# eurorack-passive-multiple.net
KiCad netlist of a schematic drawn in EAGLE
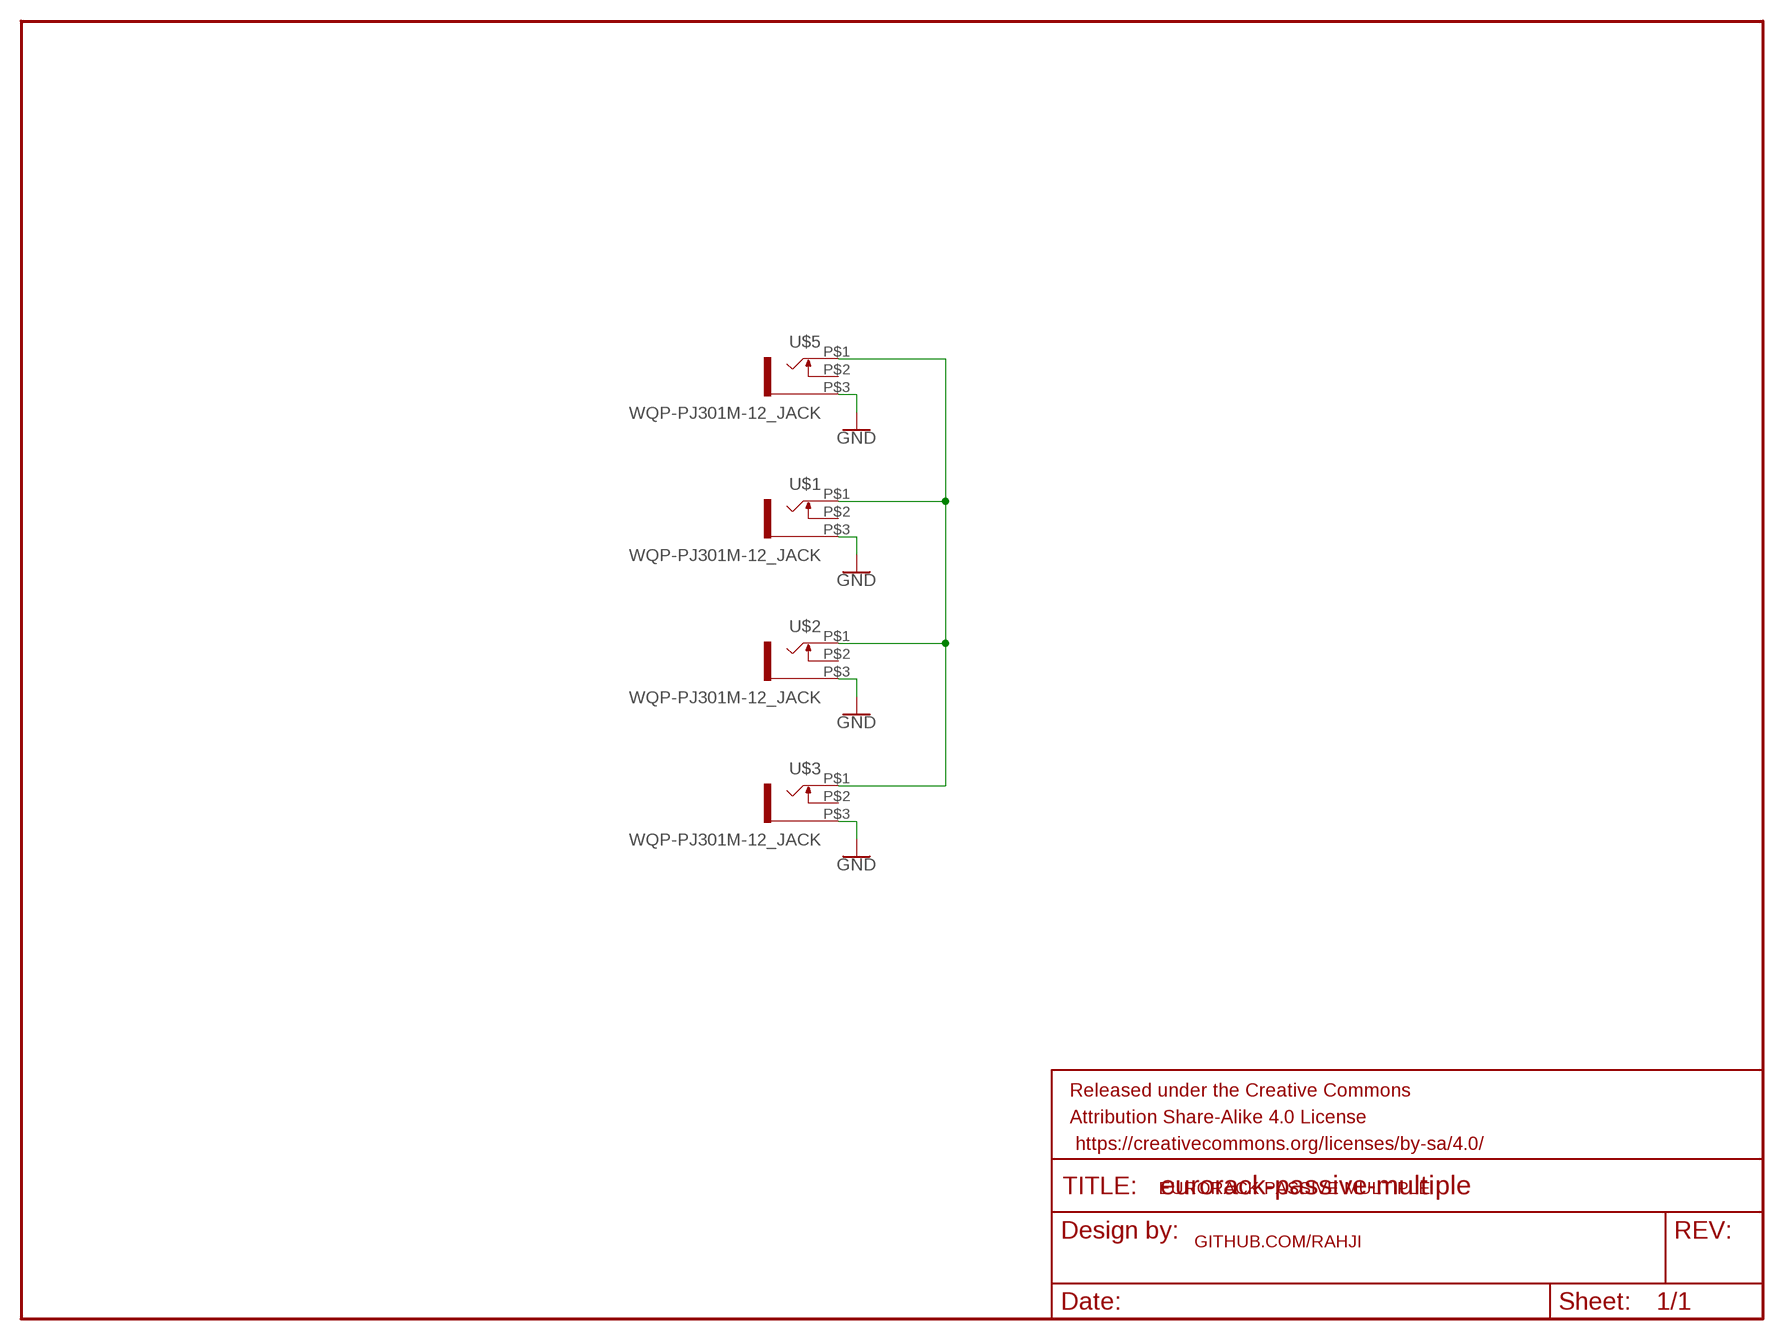
[diagram p0: schematic, sheet 1]

(export (version "E")
  (design (tool "Eeschema 10.0.6"))
  (components
    (comp (ref "FRAME1")
      (value "FRAME-LETTERNO_PACKAGE")
      (footprint "eagle-import:DUMMY")
      (fields (field (name "DESIGNER") "Nobody"))
      (libsource (lib "eagle-import") (part "FRAME-LETTERNO_PACKAGE"))
    )
    (comp (ref "U$1")
      (value "WQP-PJ301M-12_JACK")
      (footprint "eagle-import:WQP-PJ301M-12_JACK")
      (libsource (lib "eagle-import") (part "WQP-PJ301M-12_JACK"))
    )
    (comp (ref "U$2")
      (value "WQP-PJ301M-12_JACK")
      (footprint "eagle-import:WQP-PJ301M-12_JACK")
      (libsource (lib "eagle-import") (part "WQP-PJ301M-12_JACK"))
    )
    (comp (ref "U$3")
      (value "WQP-PJ301M-12_JACK")
      (footprint "eagle-import:WQP-PJ301M-12_JACK")
      (libsource (lib "eagle-import") (part "WQP-PJ301M-12_JACK"))
    )
    (comp (ref "U$5")
      (value "WQP-PJ301M-12_JACK")
      (footprint "eagle-import:WQP-PJ301M-12_JACK")
      (libsource (lib "eagle-import") (part "WQP-PJ301M-12_JACK"))
    )
  )
  (nets
    (net (code "1") (name "GND") (class "Default")
      (node (ref "U$1") (pin "P$3") (pinfunction "1_P$3") (pintype "passive"))
      (node (ref "U$2") (pin "P$3") (pinfunction "1_P$3") (pintype "passive"))
      (node (ref "U$3") (pin "P$3") (pinfunction "1_P$3") (pintype "passive"))
      (node (ref "U$5") (pin "P$3") (pinfunction "1_P$3") (pintype "passive"))
    )
    (net (code "2") (name "Net-(U$1-2)") (class "Default")
      (node (ref "U$1") (pin "P$1") (pinfunction "2_P$1") (pintype "passive"))
      (node (ref "U$2") (pin "P$1") (pinfunction "2_P$1") (pintype "passive"))
      (node (ref "U$3") (pin "P$1") (pinfunction "2_P$1") (pintype "passive"))
      (node (ref "U$5") (pin "P$1") (pinfunction "2_P$1") (pintype "passive"))
    )
    (net (code "3") (name "unconnected-(U$1-3-PadP$2)") (class "Default")
      (node (ref "U$1") (pin "P$2") (pinfunction "3_P$2") (pintype "passive"))
    )
    (net (code "4") (name "unconnected-(U$2-3-PadP$2)") (class "Default")
      (node (ref "U$2") (pin "P$2") (pinfunction "3_P$2") (pintype "passive"))
    )
    (net (code "5") (name "unconnected-(U$3-3-PadP$2)") (class "Default")
      (node (ref "U$3") (pin "P$2") (pinfunction "3_P$2") (pintype "passive"))
    )
    (net (code "6") (name "unconnected-(U$5-3-PadP$2)") (class "Default")
      (node (ref "U$5") (pin "P$2") (pinfunction "3_P$2") (pintype "passive"))
    )
  )
)
